# URESP_PULSER_2.net
KiCad netlist of a schematic drawn in Altium Designer
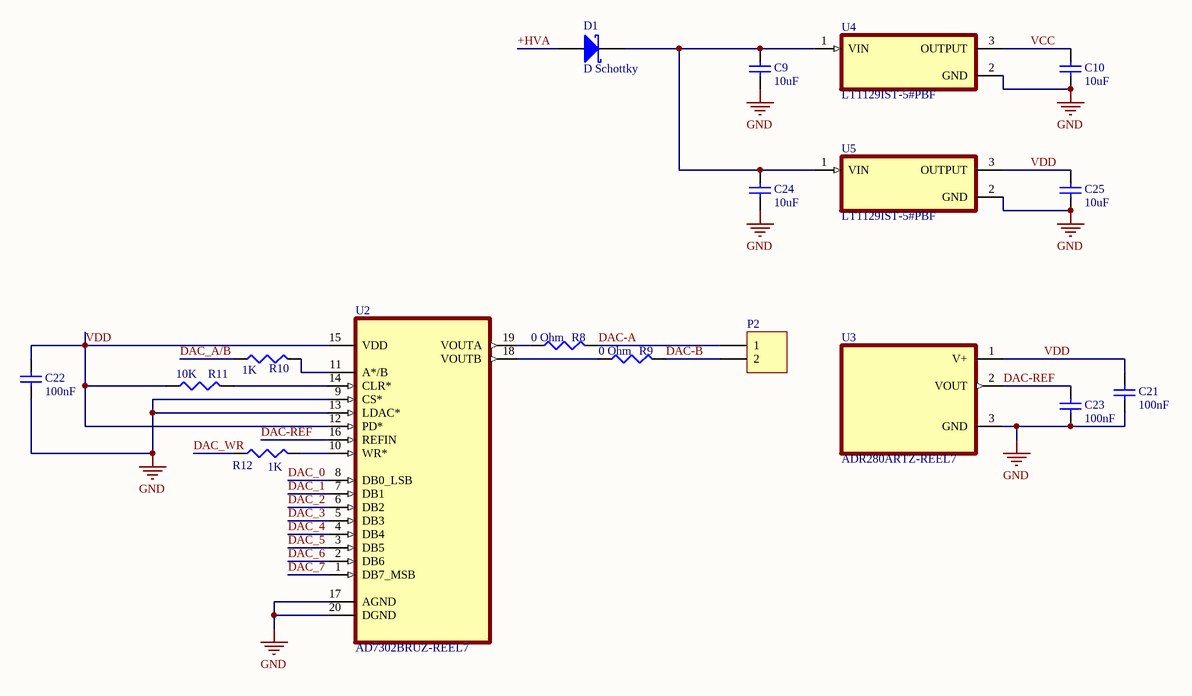
[diagram p0: URESP_PULSER_2.SchDoc]

(export (version "E")
  (design (tool "Eeschema 10.0.6"))
  (components
    (comp (ref "C9")
      (value "10uF")
      (footprint "6-0805_L")
      (description "Capacitor (Semiconductor SIM Model)")
      (fields (field (name "PUBLISHER") "Altium Limited"))
      (libsource (lib "Miscellaneous Devices") (part "Cap Semi"))
    )
    (comp (ref "C10")
      (value "10uF")
      (footprint "6-0805_L")
      (description "Capacitor (Semiconductor SIM Model)")
      (fields (field (name "PUBLISHER") "Altium Limited"))
      (libsource (lib "Miscellaneous Devices") (part "Cap Semi"))
    )
    (comp (ref "C21")
      (value "100nF")
      (footprint "1608[0603]")
      (description "Capacitor (Semiconductor SIM Model)")
      (fields (field (name "PUBLISHER") "Altium Limited"))
      (libsource (lib "Miscellaneous Devices") (part "Cap Semi"))
    )
    (comp (ref "C22")
      (value "100nF")
      (footprint "1608[0603]")
      (description "Capacitor (Semiconductor SIM Model)")
      (fields (field (name "PUBLISHER") "Altium Limited"))
      (libsource (lib "Miscellaneous Devices") (part "Cap Semi"))
    )
    (comp (ref "C23")
      (value "100nF")
      (footprint "1608[0603]")
      (description "Capacitor (Semiconductor SIM Model)")
      (fields (field (name "PUBLISHER") "Altium Limited"))
      (libsource (lib "Miscellaneous Devices") (part "Cap Semi"))
    )
    (comp (ref "C24")
      (value "10uF")
      (footprint "6-0805_L")
      (description "Capacitor (Semiconductor SIM Model)")
      (fields (field (name "PUBLISHER") "Altium Limited"))
      (libsource (lib "Miscellaneous Devices") (part "Cap Semi"))
    )
    (comp (ref "C25")
      (value "10uF")
      (footprint "6-0805_L")
      (description "Capacitor (Semiconductor SIM Model)")
      (fields (field (name "PUBLISHER") "Altium Limited"))
      (libsource (lib "Miscellaneous Devices") (part "Cap Semi"))
    )
    (comp (ref "D1")
      (value "D Schottky")
      (footprint "C1206")
      (description "Schottky Diode")
      (fields (field (name "PUBLISHER") "Altium Limited"))
      (libsource (lib "Miscellaneous Devices") (part "D Schottky"))
    )
    (comp (ref "P2")
      (value "~")
      (footprint "HDR1X2")
      (description "Header, 2-Pin")
      (fields (field (name "PUBLISHER") "Altium Limited"))
      (libsource (lib "Miscellaneous Connectors") (part "Header 2"))
    )
    (comp (ref "R8")
      (value "0 Ohm")
      (footprint "J1-0603")
      (description "Resistor")
      (fields (field (name "PUBLISHER") "Altium Limited"))
      (libsource (lib "Miscellaneous Devices") (part "Res3"))
    )
    (comp (ref "R9")
      (value "0 Ohm")
      (footprint "J1-0603")
      (description "Resistor")
      (fields (field (name "PUBLISHER") "Altium Limited"))
      (libsource (lib "Miscellaneous Devices") (part "Res3"))
    )
    (comp (ref "R10")
      (value "1K")
      (footprint "J1-0603")
      (description "Resistor")
      (fields (field (name "PUBLISHER") "Altium Limited"))
      (libsource (lib "Miscellaneous Devices") (part "Res3"))
    )
    (comp (ref "R11")
      (value "10K")
      (footprint "J1-0603")
      (description "Resistor")
      (fields (field (name "PUBLISHER") "Altium Limited"))
      (libsource (lib "Miscellaneous Devices") (part "Res3"))
    )
    (comp (ref "R12")
      (value "1K")
      (footprint "J1-0603")
      (description "Resistor")
      (fields (field (name "PUBLISHER") "Altium Limited"))
      (libsource (lib "Miscellaneous Devices") (part "Res3"))
    )
    (comp (ref "U2")
      (value "AD7302BRUZ-REEL7")
      (footprint "SOP65P637X110-20N")
      (description "8-Bit Digital-to-Analog Converters")
      (fields (field (name "MF") "{'manufacturer': u'Analog Devices'}"))
      (libsource (lib "AD7302BRUZ") (part "AD7302BRUZ-REEL7"))
    )
    (comp (ref "U3")
      (value "ADR280ARTZ-REEL7")
      (footprint "SOT96P237X112-3N")
      (fields (field (name "MF") "{'manufacturer': u'Analog Devices'}"))
      (libsource (lib "ADR280ARTZ") (part "ADR280ARTZ-REEL7"))
    )
    (comp (ref "U4")
      (value "LT1129IST-5#PBF")
      (footprint "LT1129IST-5#PBF:SOT230P700X180-4N")
      (fields (field (name "MF") "{'manufacturer': u'Analog Devices'}"))
      (libsource (lib "LT1129IST-5#PBF") (part "LT1129IST-5#PBF"))
    )
    (comp (ref "U5")
      (value "LT1129IST-5#PBF")
      (footprint "LT1129IST-5#PBF:SOT230P700X180-4N")
      (fields (field (name "MF") "{'manufacturer': u'Analog Devices'}"))
      (libsource (lib "LT1129IST-5#PBF") (part "LT1129IST-5#PBF"))
    )
  )
  (nets
    (net (code "1") (name "/+HVA") (class "Default")
      (node (ref "D1") (pin "1") (pinfunction "A_1") (pintype "passive"))
    )
    (net (code "2") (name "/DAC-A") (class "Default")
      (node (ref "P2") (pin "1") (pinfunction "1_1") (pintype "passive"))
      (node (ref "R8") (pin "2") (pinfunction "2_2") (pintype "passive"))
    )
    (net (code "3") (name "/DAC-B") (class "Default")
      (node (ref "P2") (pin "2") (pinfunction "2_2") (pintype "passive"))
      (node (ref "R9") (pin "2") (pinfunction "2_2") (pintype "passive"))
    )
    (net (code "4") (name "/DAC-REF") (class "Default")
      (node (ref "C23") (pin "2") (pinfunction "2_2") (pintype "passive"))
      (node (ref "U2") (pin "16") (pinfunction "REFIN_16") (pintype "input"))
      (node (ref "U3") (pin "2") (pinfunction "VOUT_2") (pintype "output"))
    )
    (net (code "5") (name "/DAC_0") (class "Default")
      (node (ref "U2") (pin "8") (pinfunction "DB0_LSB_8") (pintype "input"))
    )
    (net (code "6") (name "/DAC_1") (class "Default")
      (node (ref "U2") (pin "7") (pinfunction "DB1_7") (pintype "input"))
    )
    (net (code "7") (name "/DAC_2") (class "Default")
      (node (ref "U2") (pin "6") (pinfunction "DB2_6") (pintype "input"))
    )
    (net (code "8") (name "/DAC_3") (class "Default")
      (node (ref "U2") (pin "5") (pinfunction "DB3_5") (pintype "input"))
    )
    (net (code "9") (name "/DAC_4") (class "Default")
      (node (ref "U2") (pin "4") (pinfunction "DB4_4") (pintype "input"))
    )
    (net (code "10") (name "/DAC_5") (class "Default")
      (node (ref "U2") (pin "3") (pinfunction "DB5_3") (pintype "input"))
    )
    (net (code "11") (name "/DAC_6") (class "Default")
      (node (ref "U2") (pin "2") (pinfunction "DB6_2") (pintype "input"))
    )
    (net (code "12") (name "/DAC_7") (class "Default")
      (node (ref "U2") (pin "1") (pinfunction "DB7_MSB_1") (pintype "input"))
    )
    (net (code "13") (name "/DAC_A{slash}B") (class "Default")
      (node (ref "R10") (pin "1") (pinfunction "1_1") (pintype "passive"))
    )
    (net (code "14") (name "/DAC_WR") (class "Default")
      (node (ref "R12") (pin "1") (pinfunction "1_1") (pintype "passive"))
    )
    (net (code "15") (name "/VCC") (class "Default")
      (node (ref "C10") (pin "2") (pinfunction "2_2") (pintype "passive"))
      (node (ref "U4") (pin "3") (pinfunction "OUTPUT_3") (pintype "power_in"))
    )
    (net (code "16") (name "/VDD") (class "Default")
      (node (ref "C21") (pin "2") (pinfunction "2_2") (pintype "passive"))
      (node (ref "C22") (pin "2") (pinfunction "2_2") (pintype "passive"))
      (node (ref "C25") (pin "2") (pinfunction "2_2") (pintype "passive"))
      (node (ref "R11") (pin "1") (pinfunction "1_1") (pintype "passive"))
      (node (ref "U2") (pin "12") (pinfunction "PD*_12") (pintype "input"))
      (node (ref "U2") (pin "15") (pinfunction "VDD_15") (pintype "power_in"))
      (node (ref "U3") (pin "1") (pinfunction "V+_1") (pintype "power_in"))
      (node (ref "U5") (pin "3") (pinfunction "OUTPUT_3") (pintype "power_in"))
    )
    (net (code "17") (name "GND") (class "Default")
      (node (ref "C10") (pin "1") (pinfunction "1_1") (pintype "passive"))
      (node (ref "C21") (pin "1") (pinfunction "1_1") (pintype "passive"))
      (node (ref "C22") (pin "1") (pinfunction "1_1") (pintype "passive"))
      (node (ref "C23") (pin "1") (pinfunction "1_1") (pintype "passive"))
      (node (ref "C24") (pin "1") (pinfunction "1_1") (pintype "passive"))
      (node (ref "C25") (pin "1") (pinfunction "1_1") (pintype "passive"))
      (node (ref "C9") (pin "1") (pinfunction "1_1") (pintype "passive"))
      (node (ref "U2") (pin "13") (pinfunction "LDAC*_13") (pintype "input"))
      (node (ref "U2") (pin "17") (pinfunction "AGND_17") (pintype "passive"))
      (node (ref "U2") (pin "20") (pinfunction "DGND_20") (pintype "passive"))
      (node (ref "U2") (pin "9") (pinfunction "CS*_9") (pintype "input"))
      (node (ref "U3") (pin "3") (pinfunction "GND_3") (pintype "power_in"))
      (node (ref "U4") (pin "2") (pinfunction "GND_2") (pintype "power_in"))
      (node (ref "U5") (pin "2") (pinfunction "GND_2") (pintype "power_in"))
    )
    (net (code "18") (name "Net-(D1-K)") (class "Default")
      (node (ref "C24") (pin "2") (pinfunction "2_2") (pintype "passive"))
      (node (ref "C9") (pin "2") (pinfunction "2_2") (pintype "passive"))
      (node (ref "D1") (pin "2") (pinfunction "K_2") (pintype "passive"))
      (node (ref "U4") (pin "1") (pinfunction "VIN_1") (pintype "input"))
      (node (ref "U5") (pin "1") (pinfunction "VIN_1") (pintype "input"))
    )
    (net (code "19") (name "Net-(U2-A*{slash}B)") (class "Default")
      (node (ref "R10") (pin "2") (pinfunction "2_2") (pintype "passive"))
      (node (ref "U2") (pin "11") (pinfunction "A*/B_11") (pintype "passive"))
    )
    (net (code "20") (name "Net-(U2-CLR*)") (class "Default")
      (node (ref "R11") (pin "2") (pinfunction "2_2") (pintype "passive"))
      (node (ref "U2") (pin "14") (pinfunction "CLR*_14") (pintype "input"))
    )
    (net (code "21") (name "Net-(U2-VOUTA)") (class "Default")
      (node (ref "R8") (pin "1") (pinfunction "1_1") (pintype "passive"))
      (node (ref "U2") (pin "19") (pinfunction "VOUTA_19") (pintype "output"))
    )
    (net (code "22") (name "Net-(U2-VOUTB)") (class "Default")
      (node (ref "R9") (pin "1") (pinfunction "1_1") (pintype "passive"))
      (node (ref "U2") (pin "18") (pinfunction "VOUTB_18") (pintype "output"))
    )
    (net (code "23") (name "Net-(U2-WR*)") (class "Default")
      (node (ref "R12") (pin "2") (pinfunction "2_2") (pintype "passive"))
      (node (ref "U2") (pin "10") (pinfunction "WR*_10") (pintype "input"))
    )
  )
)
